# Expansionv3.net
KiCad netlist of a schematic drawn in EAGLE
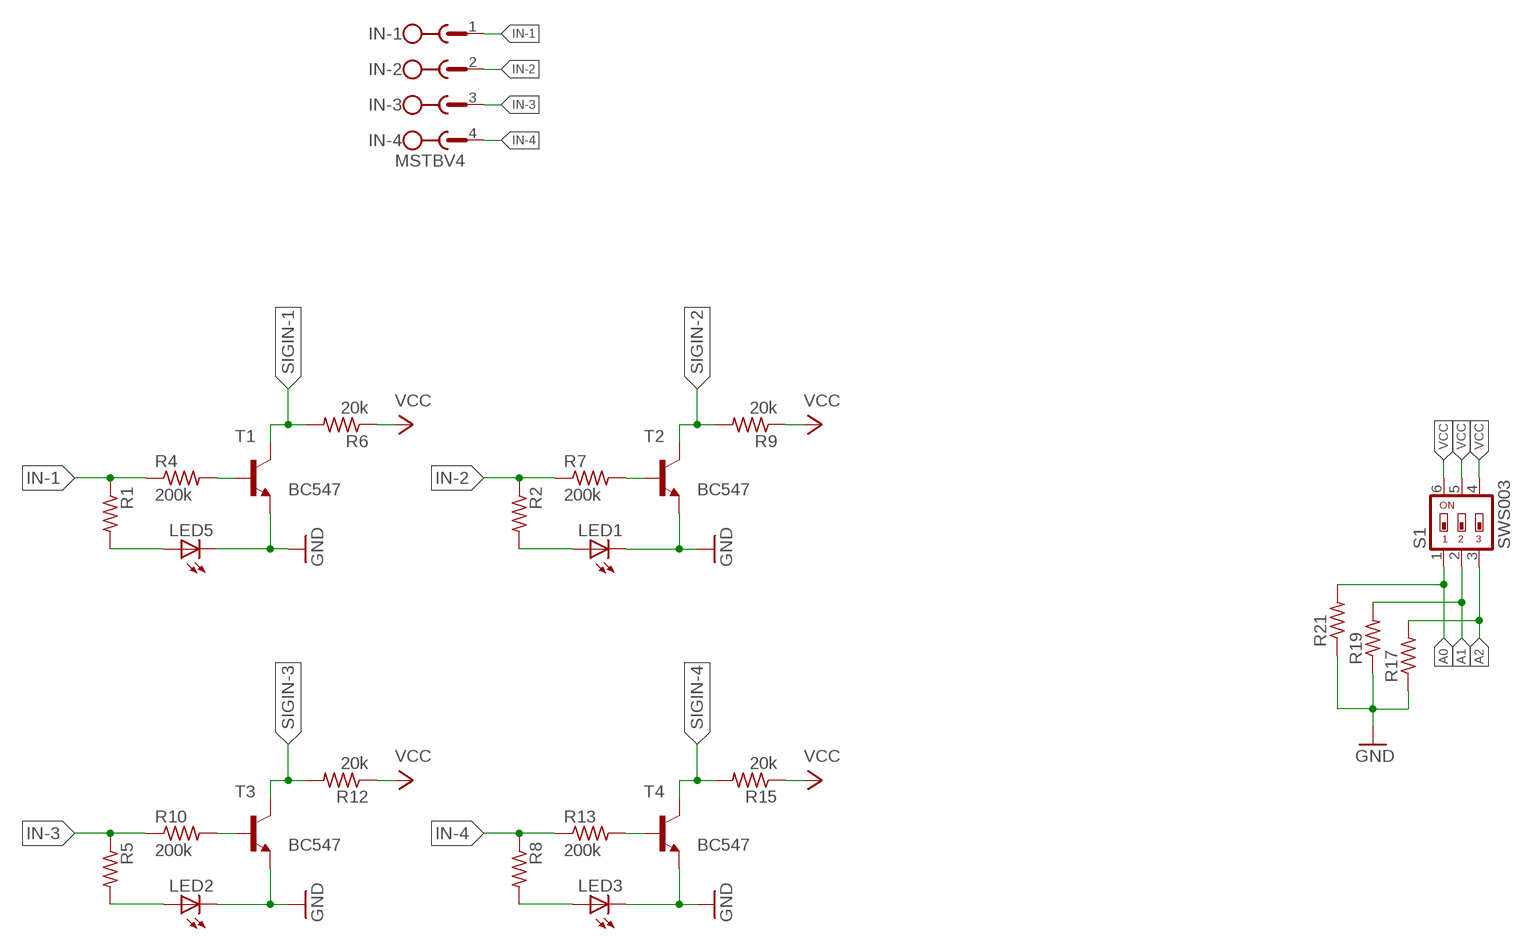
[diagram p0: schematic, sheet 1, part 1 of 2]
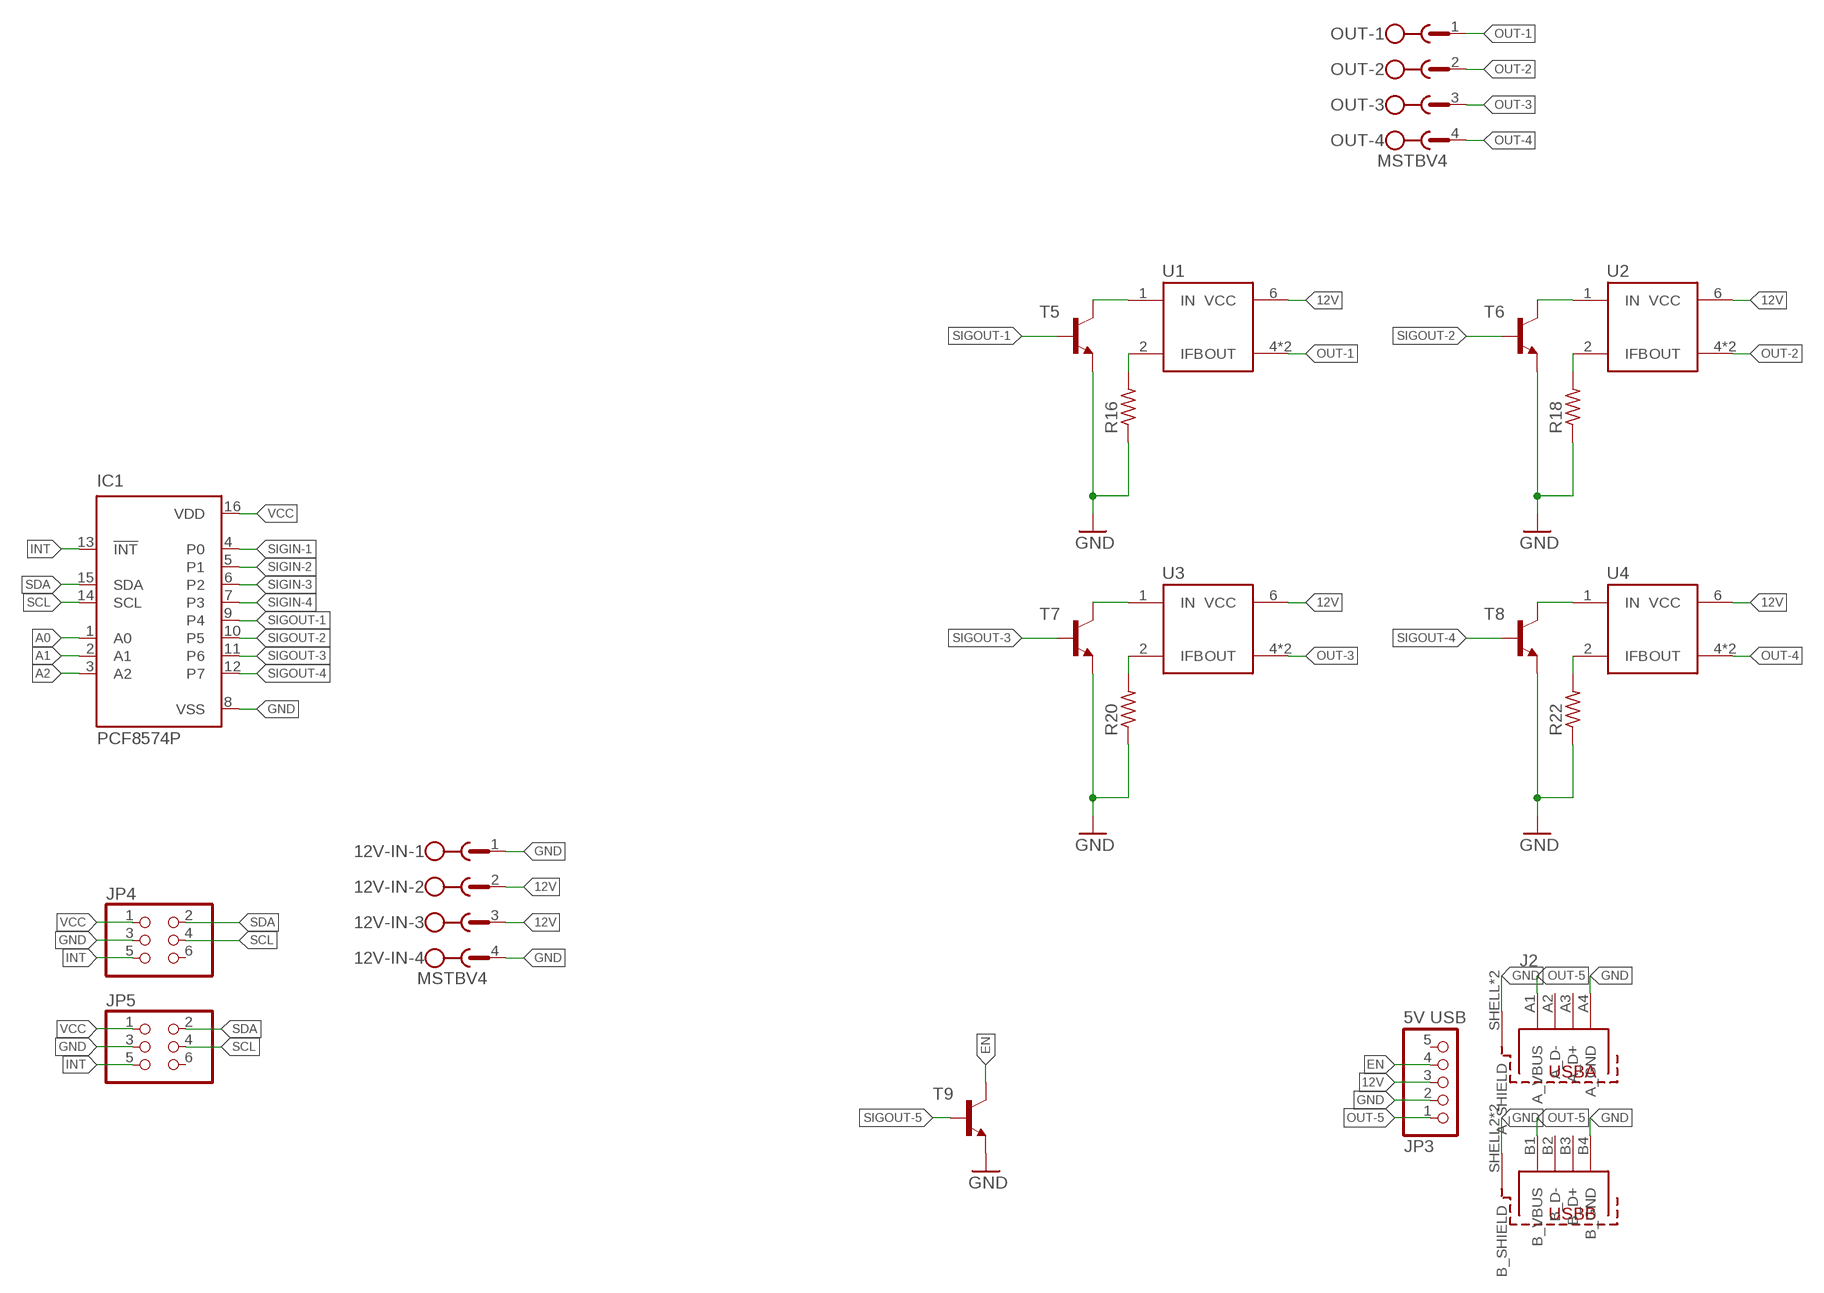
[diagram p1: schematic, sheet 1, part 2 of 2]

(export (version "E")
  (design (tool "Eeschema 10.0.6"))
  (components
    (comp (ref "12V-IN")
      (value "MSTBV4")
      (footprint "eagle-import:MSTBV4")
      (fields (field (name "MPN") "MSTBV 2,5/4-GF-5.08"))
      (libsource (lib "eagle-import") (part "MSTBV4"))
    )
    (comp (ref "IC1")
      (value "PCF8574P")
      (footprint "eagle-import:DIL16")
      (fields (field (name "MPN") "PCF8574PN"))
      (libsource (lib "eagle-import") (part "PCF8574P"))
    )
    (comp (ref "IN")
      (value "MSTBV4")
      (footprint "eagle-import:MSTBV4")
      (fields (field (name "MPN") "MSTBV 2,5/4-GF-5.08"))
      (libsource (lib "eagle-import") (part "MSTBV4"))
    )
    (comp (ref "J2")
      (value "614008235023")
      (footprint "eagle-import:614008235023")
      (libsource (lib "eagle-import") (part "614008235023"))
    )
    (comp (ref "JP3")
      (value "5V USB")
      (footprint "eagle-import:1X05")
      (libsource (lib "eagle-import") (part "PINHD-1X5"))
    )
    (comp (ref "JP4")
      (value "PINHD-2X3")
      (footprint "eagle-import:2X03")
      (libsource (lib "eagle-import") (part "PINHD-2X3"))
    )
    (comp (ref "JP5")
      (value "PINHD-2X3")
      (footprint "eagle-import:2X03")
      (libsource (lib "eagle-import") (part "PINHD-2X3"))
    )
    (comp (ref "LED1")
      (value "LEDCHIPLED_0805")
      (footprint "eagle-import:CHIPLED_0805")
      (libsource (lib "eagle-import") (part "LEDCHIPLED_0805"))
    )
    (comp (ref "LED2")
      (value "LEDCHIPLED_0805")
      (footprint "eagle-import:CHIPLED_0805")
      (libsource (lib "eagle-import") (part "LEDCHIPLED_0805"))
    )
    (comp (ref "LED3")
      (value "LEDCHIPLED_0805")
      (footprint "eagle-import:CHIPLED_0805")
      (libsource (lib "eagle-import") (part "LEDCHIPLED_0805"))
    )
    (comp (ref "LED5")
      (value "LEDCHIPLED_0805")
      (footprint "eagle-import:CHIPLED_0805")
      (libsource (lib "eagle-import") (part "LEDCHIPLED_0805"))
    )
    (comp (ref "OUT")
      (value "MSTBV4")
      (footprint "eagle-import:MSTBV4")
      (fields (field (name "MPN") "MSTBV 2,5/4-GF-5.08"))
      (libsource (lib "eagle-import") (part "MSTBV4"))
    )
    (comp (ref "R1")
      (value "R-US_R0805")
      (footprint "eagle-import:R0805")
      (libsource (lib "eagle-import") (part "R-US_R0805"))
    )
    (comp (ref "R2")
      (value "R-US_R0805")
      (footprint "eagle-import:R0805")
      (libsource (lib "eagle-import") (part "R-US_R0805"))
    )
    (comp (ref "R4")
      (value "200k")
      (footprint "eagle-import:R0805")
      (libsource (lib "eagle-import") (part "R-US_R0805"))
    )
    (comp (ref "R5")
      (value "R-US_R0805")
      (footprint "eagle-import:R0805")
      (libsource (lib "eagle-import") (part "R-US_R0805"))
    )
    (comp (ref "R6")
      (value "20k")
      (footprint "eagle-import:R0805")
      (libsource (lib "eagle-import") (part "R-US_R0805"))
    )
    (comp (ref "R7")
      (value "200k")
      (footprint "eagle-import:R0805")
      (libsource (lib "eagle-import") (part "R-US_R0805"))
    )
    (comp (ref "R8")
      (value "R-US_R0805")
      (footprint "eagle-import:R0805")
      (libsource (lib "eagle-import") (part "R-US_R0805"))
    )
    (comp (ref "R9")
      (value "20k")
      (footprint "eagle-import:R0805")
      (libsource (lib "eagle-import") (part "R-US_R0805"))
    )
    (comp (ref "R10")
      (value "200k")
      (footprint "eagle-import:R0805")
      (libsource (lib "eagle-import") (part "R-US_R0805"))
    )
    (comp (ref "R12")
      (value "20k")
      (footprint "eagle-import:R0805")
      (libsource (lib "eagle-import") (part "R-US_R0805"))
    )
    (comp (ref "R13")
      (value "200k")
      (footprint "eagle-import:R0805")
      (libsource (lib "eagle-import") (part "R-US_R0805"))
    )
    (comp (ref "R15")
      (value "20k")
      (footprint "eagle-import:R0805")
      (libsource (lib "eagle-import") (part "R-US_R0805"))
    )
    (comp (ref "R16")
      (value "R-US_R0805")
      (footprint "eagle-import:R0805")
      (libsource (lib "eagle-import") (part "R-US_R0805"))
    )
    (comp (ref "R17")
      (value "R-US_R0805")
      (footprint "eagle-import:R0805")
      (libsource (lib "eagle-import") (part "R-US_R0805"))
    )
    (comp (ref "R18")
      (value "R-US_R0805")
      (footprint "eagle-import:R0805")
      (libsource (lib "eagle-import") (part "R-US_R0805"))
    )
    (comp (ref "R19")
      (value "R-US_R0805")
      (footprint "eagle-import:R0805")
      (libsource (lib "eagle-import") (part "R-US_R0805"))
    )
    (comp (ref "R20")
      (value "R-US_R0805")
      (footprint "eagle-import:R0805")
      (libsource (lib "eagle-import") (part "R-US_R0805"))
    )
    (comp (ref "R21")
      (value "R-US_R0805")
      (footprint "eagle-import:R0805")
      (libsource (lib "eagle-import") (part "R-US_R0805"))
    )
    (comp (ref "R22")
      (value "R-US_R0805")
      (footprint "eagle-import:R0805")
      (libsource (lib "eagle-import") (part "R-US_R0805"))
    )
    (comp (ref "S1")
      (value "SWS003")
      (footprint "eagle-import:SMS-003")
      (libsource (lib "eagle-import") (part "SWS003"))
    )
    (comp (ref "T1")
      (value "BC547")
      (footprint "eagle-import:SOT23-EBC")
      (libsource (lib "eagle-import") (part "-NPN-SOT23-EBC"))
    )
    (comp (ref "T2")
      (value "BC547")
      (footprint "eagle-import:SOT23-EBC")
      (libsource (lib "eagle-import") (part "-NPN-SOT23-EBC"))
    )
    (comp (ref "T3")
      (value "BC547")
      (footprint "eagle-import:SOT23-EBC")
      (libsource (lib "eagle-import") (part "-NPN-SOT23-EBC"))
    )
    (comp (ref "T4")
      (value "BC547")
      (footprint "eagle-import:SOT23-EBC")
      (libsource (lib "eagle-import") (part "-NPN-SOT23-EBC"))
    )
    (comp (ref "T5")
      (value "-NPN-SOT23-EBC")
      (footprint "eagle-import:SOT23-EBC")
      (libsource (lib "eagle-import") (part "-NPN-SOT23-EBC"))
    )
    (comp (ref "T6")
      (value "-NPN-SOT23-EBC")
      (footprint "eagle-import:SOT23-EBC")
      (libsource (lib "eagle-import") (part "-NPN-SOT23-EBC"))
    )
    (comp (ref "T7")
      (value "-NPN-SOT23-EBC")
      (footprint "eagle-import:SOT23-EBC")
      (libsource (lib "eagle-import") (part "-NPN-SOT23-EBC"))
    )
    (comp (ref "T8")
      (value "-NPN-SOT23-EBC")
      (footprint "eagle-import:SOT23-EBC")
      (libsource (lib "eagle-import") (part "-NPN-SOT23-EBC"))
    )
    (comp (ref "T9")
      (value "-NPN-SOT23-EBC")
      (footprint "eagle-import:SOT23-EBC")
      (libsource (lib "eagle-import") (part "-NPN-SOT23-EBC"))
    )
    (comp (ref "U1")
      (value "IR3315")
      (footprint "eagle-import:TO263-5")
      (libsource (lib "eagle-import") (part "IR3315"))
    )
    (comp (ref "U2")
      (value "IR3315")
      (footprint "eagle-import:TO263-5")
      (libsource (lib "eagle-import") (part "IR3315"))
    )
    (comp (ref "U3")
      (value "IR3315")
      (footprint "eagle-import:TO263-5")
      (libsource (lib "eagle-import") (part "IR3315"))
    )
    (comp (ref "U4")
      (value "IR3315")
      (footprint "eagle-import:TO263-5")
      (libsource (lib "eagle-import") (part "IR3315"))
    )
  )
  (nets
    (net (code "1") (name "12V") (class "Default")
      (node (ref "12V-IN") (pin "2") (pinfunction "1_2") (pintype "passive"))
      (node (ref "12V-IN") (pin "3") (pinfunction "1_3") (pintype "passive"))
      (node (ref "JP3") (pin "3") (pinfunction "3_3") (pintype "passive"))
      (node (ref "U1") (pin "6") (pinfunction "VCC_6") (pintype "bidirectional"))
      (node (ref "U2") (pin "6") (pinfunction "VCC_6") (pintype "bidirectional"))
      (node (ref "U3") (pin "6") (pinfunction "VCC_6") (pintype "bidirectional"))
      (node (ref "U4") (pin "6") (pinfunction "VCC_6") (pintype "bidirectional"))
    )
    (net (code "2") (name "A0") (class "Default")
      (node (ref "IC1") (pin "1") (pinfunction "A0_1") (pintype "input"))
      (node (ref "R21") (pin "2") (pinfunction "2_2") (pintype "passive"))
      (node (ref "S1") (pin "1") (pinfunction "1_1") (pintype "passive"))
    )
    (net (code "3") (name "A1") (class "Default")
      (node (ref "IC1") (pin "2") (pinfunction "A1_2") (pintype "input"))
      (node (ref "R19") (pin "2") (pinfunction "2_2") (pintype "passive"))
      (node (ref "S1") (pin "2") (pinfunction "2_2") (pintype "passive"))
    )
    (net (code "4") (name "A2") (class "Default")
      (node (ref "IC1") (pin "3") (pinfunction "A2_3") (pintype "input"))
      (node (ref "R17") (pin "2") (pinfunction "2_2") (pintype "passive"))
      (node (ref "S1") (pin "3") (pinfunction "3_3") (pintype "passive"))
    )
    (net (code "5") (name "EN") (class "Default")
      (node (ref "JP3") (pin "4") (pinfunction "4_4") (pintype "passive"))
      (node (ref "T9") (pin "C") (pinfunction "C_C") (pintype "passive"))
    )
    (net (code "6") (name "GND") (class "Default")
      (node (ref "12V-IN") (pin "1") (pinfunction "1_1") (pintype "passive"))
      (node (ref "12V-IN") (pin "4") (pinfunction "1_4") (pintype "passive"))
      (node (ref "IC1") (pin "8") (pinfunction "VSS_8") (pintype "power_in"))
      (node (ref "J2") (pin "A4") (pinfunction "A_GND_A4") (pintype "bidirectional"))
      (node (ref "J2") (pin "B4") (pinfunction "B_GND_B4") (pintype "bidirectional"))
      (node (ref "J2") (pin "SHELL") (pinfunction "A_SHIELD_SHELL") (pintype "bidirectional"))
      (node (ref "J2") (pin "SHELL1") (pinfunction "A_SHIELD_SHELL1") (pintype "bidirectional"))
      (node (ref "J2") (pin "SHELL2") (pinfunction "B_SHIELD_SHELL2") (pintype "bidirectional"))
      (node (ref "J2") (pin "SHELL3") (pinfunction "B_SHIELD_SHELL3") (pintype "bidirectional"))
      (node (ref "JP3") (pin "2") (pinfunction "2_2") (pintype "passive"))
      (node (ref "JP4") (pin "3") (pinfunction "3_3") (pintype "passive"))
      (node (ref "JP5") (pin "3") (pinfunction "3_3") (pintype "passive"))
      (node (ref "LED1") (pin "C") (pinfunction "C_C") (pintype "passive"))
      (node (ref "LED2") (pin "C") (pinfunction "C_C") (pintype "passive"))
      (node (ref "LED3") (pin "C") (pinfunction "C_C") (pintype "passive"))
      (node (ref "LED5") (pin "C") (pinfunction "C_C") (pintype "passive"))
      (node (ref "R16") (pin "1") (pinfunction "1_1") (pintype "passive"))
      (node (ref "R17") (pin "1") (pinfunction "1_1") (pintype "passive"))
      (node (ref "R18") (pin "1") (pinfunction "1_1") (pintype "passive"))
      (node (ref "R19") (pin "1") (pinfunction "1_1") (pintype "passive"))
      (node (ref "R20") (pin "1") (pinfunction "1_1") (pintype "passive"))
      (node (ref "R21") (pin "1") (pinfunction "1_1") (pintype "passive"))
      (node (ref "R22") (pin "1") (pinfunction "1_1") (pintype "passive"))
      (node (ref "T1") (pin "E") (pinfunction "E_E") (pintype "passive"))
      (node (ref "T2") (pin "E") (pinfunction "E_E") (pintype "passive"))
      (node (ref "T3") (pin "E") (pinfunction "E_E") (pintype "passive"))
      (node (ref "T4") (pin "E") (pinfunction "E_E") (pintype "passive"))
      (node (ref "T5") (pin "E") (pinfunction "E_E") (pintype "passive"))
      (node (ref "T6") (pin "E") (pinfunction "E_E") (pintype "passive"))
      (node (ref "T7") (pin "E") (pinfunction "E_E") (pintype "passive"))
      (node (ref "T8") (pin "E") (pinfunction "E_E") (pintype "passive"))
      (node (ref "T9") (pin "E") (pinfunction "E_E") (pintype "passive"))
    )
    (net (code "7") (name "IN-1") (class "Default")
      (node (ref "IN") (pin "1") (pinfunction "1_1") (pintype "passive"))
      (node (ref "R1") (pin "1") (pinfunction "1_1") (pintype "passive"))
      (node (ref "R4") (pin "1") (pinfunction "1_1") (pintype "passive"))
    )
    (net (code "8") (name "IN-2") (class "Default")
      (node (ref "IN") (pin "2") (pinfunction "1_2") (pintype "passive"))
      (node (ref "R2") (pin "1") (pinfunction "1_1") (pintype "passive"))
      (node (ref "R7") (pin "1") (pinfunction "1_1") (pintype "passive"))
    )
    (net (code "9") (name "IN-3") (class "Default")
      (node (ref "IN") (pin "3") (pinfunction "1_3") (pintype "passive"))
      (node (ref "R10") (pin "1") (pinfunction "1_1") (pintype "passive"))
      (node (ref "R5") (pin "1") (pinfunction "1_1") (pintype "passive"))
    )
    (net (code "10") (name "IN-4") (class "Default")
      (node (ref "IN") (pin "4") (pinfunction "1_4") (pintype "passive"))
      (node (ref "R13") (pin "1") (pinfunction "1_1") (pintype "passive"))
      (node (ref "R8") (pin "1") (pinfunction "1_1") (pintype "passive"))
    )
    (net (code "11") (name "INT") (class "Default")
      (node (ref "IC1") (pin "13") (pinfunction "~{INT}_13") (pintype "output"))
      (node (ref "JP4") (pin "5") (pinfunction "5_5") (pintype "passive"))
      (node (ref "JP5") (pin "5") (pinfunction "5_5") (pintype "passive"))
    )
    (net (code "12") (name "Net-(LED1-PadA)") (class "Default")
      (node (ref "LED1") (pin "A") (pinfunction "A_A") (pintype "passive"))
      (node (ref "R2") (pin "2") (pinfunction "2_2") (pintype "passive"))
    )
    (net (code "13") (name "Net-(LED2-PadA)") (class "Default")
      (node (ref "LED2") (pin "A") (pinfunction "A_A") (pintype "passive"))
      (node (ref "R5") (pin "2") (pinfunction "2_2") (pintype "passive"))
    )
    (net (code "14") (name "Net-(LED3-PadA)") (class "Default")
      (node (ref "LED3") (pin "A") (pinfunction "A_A") (pintype "passive"))
      (node (ref "R8") (pin "2") (pinfunction "2_2") (pintype "passive"))
    )
    (net (code "15") (name "Net-(LED5-PadA)") (class "Default")
      (node (ref "LED5") (pin "A") (pinfunction "A_A") (pintype "passive"))
      (node (ref "R1") (pin "2") (pinfunction "2_2") (pintype "passive"))
    )
    (net (code "16") (name "Net-(R4-Pad2)") (class "Default")
      (node (ref "R4") (pin "2") (pinfunction "2_2") (pintype "passive"))
      (node (ref "T1") (pin "B") (pinfunction "B_B") (pintype "passive"))
    )
    (net (code "17") (name "Net-(R7-Pad2)") (class "Default")
      (node (ref "R7") (pin "2") (pinfunction "2_2") (pintype "passive"))
      (node (ref "T2") (pin "B") (pinfunction "B_B") (pintype "passive"))
    )
    (net (code "18") (name "Net-(R10-Pad2)") (class "Default")
      (node (ref "R10") (pin "2") (pinfunction "2_2") (pintype "passive"))
      (node (ref "T3") (pin "B") (pinfunction "B_B") (pintype "passive"))
    )
    (net (code "19") (name "Net-(R13-Pad2)") (class "Default")
      (node (ref "R13") (pin "2") (pinfunction "2_2") (pintype "passive"))
      (node (ref "T4") (pin "B") (pinfunction "B_B") (pintype "passive"))
    )
    (net (code "20") (name "Net-(U1-IFB)") (class "Default")
      (node (ref "R16") (pin "2") (pinfunction "2_2") (pintype "passive"))
      (node (ref "U1") (pin "2") (pinfunction "IFB_2") (pintype "bidirectional"))
    )
    (net (code "21") (name "Net-(U1-IN)") (class "Default")
      (node (ref "T5") (pin "C") (pinfunction "C_C") (pintype "passive"))
      (node (ref "U1") (pin "1") (pinfunction "IN_1") (pintype "bidirectional"))
    )
    (net (code "22") (name "Net-(U2-IFB)") (class "Default")
      (node (ref "R18") (pin "2") (pinfunction "2_2") (pintype "passive"))
      (node (ref "U2") (pin "2") (pinfunction "IFB_2") (pintype "bidirectional"))
    )
    (net (code "23") (name "Net-(U2-IN)") (class "Default")
      (node (ref "T6") (pin "C") (pinfunction "C_C") (pintype "passive"))
      (node (ref "U2") (pin "1") (pinfunction "IN_1") (pintype "bidirectional"))
    )
    (net (code "24") (name "Net-(U3-IFB)") (class "Default")
      (node (ref "R20") (pin "2") (pinfunction "2_2") (pintype "passive"))
      (node (ref "U3") (pin "2") (pinfunction "IFB_2") (pintype "bidirectional"))
    )
    (net (code "25") (name "Net-(U3-IN)") (class "Default")
      (node (ref "T7") (pin "C") (pinfunction "C_C") (pintype "passive"))
      (node (ref "U3") (pin "1") (pinfunction "IN_1") (pintype "bidirectional"))
    )
    (net (code "26") (name "Net-(U4-IFB)") (class "Default")
      (node (ref "R22") (pin "2") (pinfunction "2_2") (pintype "passive"))
      (node (ref "U4") (pin "2") (pinfunction "IFB_2") (pintype "bidirectional"))
    )
    (net (code "27") (name "Net-(U4-IN)") (class "Default")
      (node (ref "T8") (pin "C") (pinfunction "C_C") (pintype "passive"))
      (node (ref "U4") (pin "1") (pinfunction "IN_1") (pintype "bidirectional"))
    )
    (net (code "28") (name "OUT-1") (class "Default")
      (node (ref "OUT") (pin "1") (pinfunction "1_1") (pintype "passive"))
      (node (ref "U1") (pin "4") (pinfunction "OUT_4") (pintype "bidirectional"))
      (node (ref "U1") (pin "5") (pinfunction "OUT_5") (pintype "bidirectional"))
    )
    (net (code "29") (name "OUT-2") (class "Default")
      (node (ref "OUT") (pin "2") (pinfunction "1_2") (pintype "passive"))
      (node (ref "U2") (pin "4") (pinfunction "OUT_4") (pintype "bidirectional"))
      (node (ref "U2") (pin "5") (pinfunction "OUT_5") (pintype "bidirectional"))
    )
    (net (code "30") (name "OUT-3") (class "Default")
      (node (ref "OUT") (pin "3") (pinfunction "1_3") (pintype "passive"))
      (node (ref "U3") (pin "4") (pinfunction "OUT_4") (pintype "bidirectional"))
      (node (ref "U3") (pin "5") (pinfunction "OUT_5") (pintype "bidirectional"))
    )
    (net (code "31") (name "OUT-4") (class "Default")
      (node (ref "OUT") (pin "4") (pinfunction "1_4") (pintype "passive"))
      (node (ref "U4") (pin "4") (pinfunction "OUT_4") (pintype "bidirectional"))
      (node (ref "U4") (pin "5") (pinfunction "OUT_5") (pintype "bidirectional"))
    )
    (net (code "32") (name "OUT-5") (class "Default")
      (node (ref "J2") (pin "A1") (pinfunction "A_VBUS_A1") (pintype "bidirectional"))
      (node (ref "J2") (pin "B1") (pinfunction "B_VBUS_B1") (pintype "bidirectional"))
      (node (ref "JP3") (pin "1") (pinfunction "1_1") (pintype "passive"))
    )
    (net (code "33") (name "SCL") (class "Default")
      (node (ref "IC1") (pin "14") (pinfunction "SCL_14") (pintype "input"))
      (node (ref "JP4") (pin "4") (pinfunction "4_4") (pintype "passive"))
      (node (ref "JP5") (pin "4") (pinfunction "4_4") (pintype "passive"))
    )
    (net (code "34") (name "SDA") (class "Default")
      (node (ref "IC1") (pin "15") (pinfunction "SDA_15") (pintype "bidirectional"))
      (node (ref "JP4") (pin "2") (pinfunction "2_2") (pintype "passive"))
      (node (ref "JP5") (pin "2") (pinfunction "2_2") (pintype "passive"))
    )
    (net (code "35") (name "SIGIN-1") (class "Default")
      (node (ref "IC1") (pin "4") (pinfunction "P0_4") (pintype "bidirectional"))
      (node (ref "R6") (pin "2") (pinfunction "2_2") (pintype "passive"))
      (node (ref "T1") (pin "C") (pinfunction "C_C") (pintype "passive"))
    )
    (net (code "36") (name "SIGIN-2") (class "Default")
      (node (ref "IC1") (pin "5") (pinfunction "P1_5") (pintype "bidirectional"))
      (node (ref "R9") (pin "2") (pinfunction "2_2") (pintype "passive"))
      (node (ref "T2") (pin "C") (pinfunction "C_C") (pintype "passive"))
    )
    (net (code "37") (name "SIGIN-3") (class "Default")
      (node (ref "IC1") (pin "6") (pinfunction "P2_6") (pintype "bidirectional"))
      (node (ref "R12") (pin "2") (pinfunction "2_2") (pintype "passive"))
      (node (ref "T3") (pin "C") (pinfunction "C_C") (pintype "passive"))
    )
    (net (code "38") (name "SIGIN-4") (class "Default")
      (node (ref "IC1") (pin "7") (pinfunction "P3_7") (pintype "bidirectional"))
      (node (ref "R15") (pin "2") (pinfunction "2_2") (pintype "passive"))
      (node (ref "T4") (pin "C") (pinfunction "C_C") (pintype "passive"))
    )
    (net (code "39") (name "SIGOUT-1") (class "Default")
      (node (ref "IC1") (pin "9") (pinfunction "P4_9") (pintype "bidirectional"))
      (node (ref "T5") (pin "B") (pinfunction "B_B") (pintype "passive"))
    )
    (net (code "40") (name "SIGOUT-2") (class "Default")
      (node (ref "IC1") (pin "10") (pinfunction "P5_10") (pintype "bidirectional"))
      (node (ref "T6") (pin "B") (pinfunction "B_B") (pintype "passive"))
    )
    (net (code "41") (name "SIGOUT-3") (class "Default")
      (node (ref "IC1") (pin "11") (pinfunction "P6_11") (pintype "bidirectional"))
      (node (ref "T7") (pin "B") (pinfunction "B_B") (pintype "passive"))
    )
    (net (code "42") (name "SIGOUT-4") (class "Default")
      (node (ref "IC1") (pin "12") (pinfunction "P7_12") (pintype "bidirectional"))
      (node (ref "T8") (pin "B") (pinfunction "B_B") (pintype "passive"))
    )
    (net (code "43") (name "SIGOUT-5") (class "Default")
      (node (ref "T9") (pin "B") (pinfunction "B_B") (pintype "passive"))
    )
    (net (code "44") (name "VCC") (class "Default")
      (node (ref "IC1") (pin "16") (pinfunction "VDD_16") (pintype "power_in"))
      (node (ref "JP4") (pin "1") (pinfunction "1_1") (pintype "passive"))
      (node (ref "JP5") (pin "1") (pinfunction "1_1") (pintype "passive"))
      (node (ref "R12") (pin "1") (pinfunction "1_1") (pintype "passive"))
      (node (ref "R15") (pin "1") (pinfunction "1_1") (pintype "passive"))
      (node (ref "R6") (pin "1") (pinfunction "1_1") (pintype "passive"))
      (node (ref "R9") (pin "1") (pinfunction "1_1") (pintype "passive"))
      (node (ref "S1") (pin "4") (pinfunction "4_4") (pintype "passive"))
      (node (ref "S1") (pin "5") (pinfunction "5_5") (pintype "passive"))
      (node (ref "S1") (pin "6") (pinfunction "6_6") (pintype "passive"))
    )
    (net (code "45") (name "unconnected-(J2-A_D+-PadA3)") (class "Default")
      (node (ref "J2") (pin "A3") (pinfunction "A_D+_A3") (pintype "bidirectional"))
    )
    (net (code "46") (name "unconnected-(J2-A_D--PadA2)") (class "Default")
      (node (ref "J2") (pin "A2") (pinfunction "A_D-_A2") (pintype "bidirectional"))
    )
    (net (code "47") (name "unconnected-(J2-B_D+-PadB3)") (class "Default")
      (node (ref "J2") (pin "B3") (pinfunction "B_D+_B3") (pintype "bidirectional"))
    )
    (net (code "48") (name "unconnected-(J2-B_D--PadB2)") (class "Default")
      (node (ref "J2") (pin "B2") (pinfunction "B_D-_B2") (pintype "bidirectional"))
    )
    (net (code "49") (name "unconnected-(JP3-Pad5)") (class "Default")
      (node (ref "JP3") (pin "5") (pinfunction "5_5") (pintype "passive"))
    )
    (net (code "50") (name "unconnected-(JP4-Pad6)") (class "Default")
      (node (ref "JP4") (pin "6") (pinfunction "6_6") (pintype "passive"))
    )
    (net (code "51") (name "unconnected-(JP5-Pad6)") (class "Default")
      (node (ref "JP5") (pin "6") (pinfunction "6_6") (pintype "passive"))
    )
  )
)
